# USB_Serial.net
KiCad netlist of a schematic drawn in Altium Designer
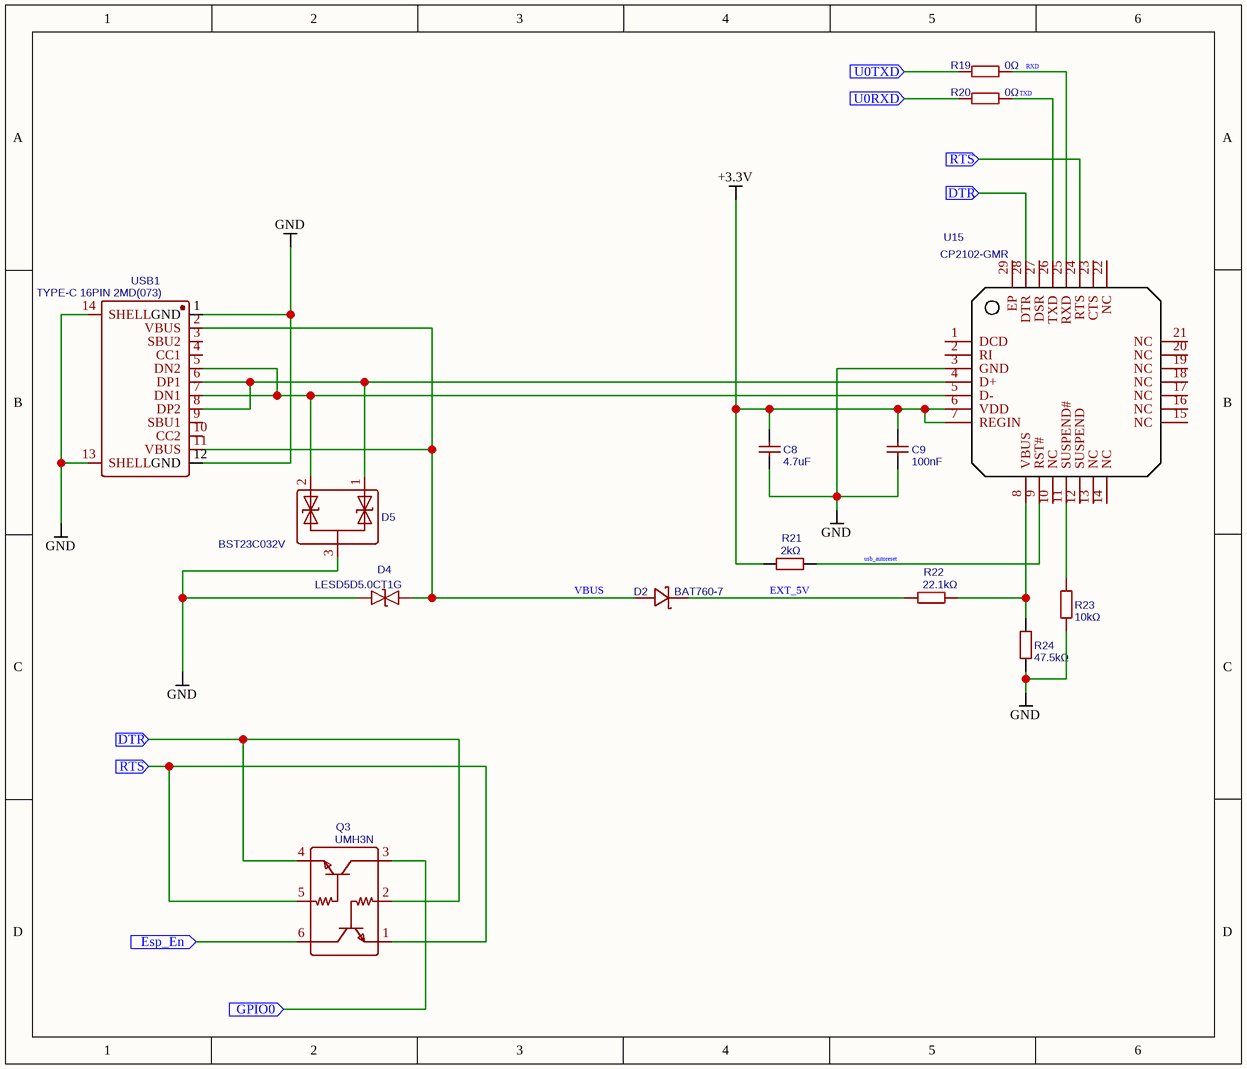
[diagram p0: USB_Serial.schdoc]

(export (version "E")
  (design (tool "Eeschema 10.0.6"))
  (components
    (comp (ref "C8")
      (value "4.7uF")
      (fields (field (name "MANUFACTURER") "FH") (field (name "MANUFACTURER PART") "0603X475K160NT"))
      (libsource (lib "altium-import") (part "root_1_4.7uF_"))
    )
    (comp (ref "C9")
      (value "100nF")
      (fields (field (name "MANUFACTURER") "SAMSUNG") (field (name "MANUFACTURER PART") "CL10B104KO8NNNC"))
      (libsource (lib "altium-import") (part "root_1_100nF_"))
    )
    (comp (ref "D2")
      (value "BAT760-7")
      (fields (field (name "MANUFACTURER") "DIODES") (field (name "CONTRIBUTOR") "LCSC"))
      (libsource (lib "altium-import") (part "root_2_BAT760-7_"))
    )
    (comp (ref "D4")
      (value "LESD5D5.0CT1G")
      (fields (field (name "MANUFACTURER") "Leshan Radio") (field (name "CONTRIBUTOR") "LCSC"))
      (libsource (lib "altium-import") (part "root_0_LESD5D5.0CT1G_"))
    )
    (comp (ref "D5")
      (value "BST23C032V")
      (fields (field (name "MANUFACTURER") "Bourne Semicon (Shenzhen)") (field (name "CONTRIBUTOR") "LCSC"))
      (libsource (lib "altium-import") (part "root_2_BST23C032V_"))
    )
    (comp (ref "Q3")
      (value "UMH3N")
      (fields (field (name "MANUFACTURER") "CJ"))
      (libsource (lib "altium-import") (part "root_1_UMH3N_"))
    )
    (comp (ref "R19")
      (value "0Ω")
      (fields
        (field (name "MANUFACTURER") "FH")
        (field (name "MANUFACTURER PART") "RS-03000FT")
        (field (name "CONTRIBUTOR") "LCSC")
      )
      (libsource (lib "altium-import") (part "root_0_0Ω_"))
    )
    (comp (ref "R20")
      (value "0Ω")
      (fields
        (field (name "MANUFACTURER") "FH")
        (field (name "MANUFACTURER PART") "RS-03000FT")
        (field (name "CONTRIBUTOR") "LCSC")
      )
      (libsource (lib "altium-import") (part "root_0_0Ω_"))
    )
    (comp (ref "R21")
      (value "2kΩ")
      (fields (field (name "MANUFACTURER") "FH") (field (name "MANUFACTURER PART") "RS-03K2001FT"))
      (libsource (lib "altium-import") (part "root_0_2kΩ_"))
    )
    (comp (ref "R22")
      (value "22.1kΩ")
      (fields
        (field (name "MANUFACTURER") "Guangdong Fenghua Advanced Tech")
        (field (name "MANUFACTURER PART") "RS-03K2212FT")
        (field (name "CONTRIBUTOR") "LCSC")
      )
      (libsource (lib "altium-import") (part "root_0_22.1kΩ_"))
    )
    (comp (ref "R23")
      (value "10kΩ")
      (fields
        (field (name "MANUFACTURER") "Guangdong Fenghua Advanced Tech")
        (field (name "MANUFACTURER PART") "RS-03K1002FT")
        (field (name "CONTRIBUTOR") "LCSC")
      )
      (libsource (lib "altium-import") (part "root_1_10kΩ_"))
    )
    (comp (ref "R24")
      (value "47.5kΩ")
      (fields (field (name "MANUFACTURER") "UniOhm") (field (name "MANUFACTURER PART") "0603WAF4752T5E"))
      (libsource (lib "altium-import") (part "root_1_47.5kΩ_"))
    )
    (comp (ref "U15")
      (value "CP2102-GMR")
      (fields (field (name "MANUFACTURER") "SILICON LABS"))
      (libsource (lib "altium-import") (part "root_0_CP2102-GMR_"))
    )
    (comp (ref "USB1")
      (value "TYPE-C 16PIN 2MD(073)")
      (fields (field (name "MANUFACTURER") "SHOU HAN(首韩)") (field (name "CONTRIBUTOR") "LCSC"))
      (libsource (lib "altium-import") (part "root_0_TYPE-C 16PIN 2MD(073)_"))
    )
  )
  (nets
    (net (code "1") (name "+3.3V") (class "Default")
      (node (ref "C8") (pin "2") (pinfunction "2_2") (pintype "passive"))
      (node (ref "C9") (pin "2") (pinfunction "2_2") (pintype "passive"))
      (node (ref "R21") (pin "1") (pinfunction "1_1") (pintype "passive"))
      (node (ref "U15") (pin "6") (pinfunction "VDD_6") (pintype "passive"))
      (node (ref "U15") (pin "7") (pinfunction "REGIN_7") (pintype "passive"))
    )
    (net (code "2") (name "/DTR") (class "Default")
      (node (ref "Q3") (pin "2") (pinfunction "B_2") (pintype "passive"))
      (node (ref "Q3") (pin "4") (pinfunction "E_4") (pintype "passive"))
      (node (ref "U15") (pin "28") (pinfunction "DTR_28") (pintype "passive"))
    )
    (net (code "3") (name "/EXT_5V") (class "Default")
      (node (ref "D2") (pin "1") (pinfunction "1_1") (pintype "passive"))
      (node (ref "R22") (pin "1") (pinfunction "1_1") (pintype "passive"))
    )
    (net (code "4") (name "/Esp_En") (class "Default")
      (node (ref "Q3") (pin "6") (pinfunction "C_6") (pintype "passive"))
    )
    (net (code "5") (name "/GPIO0") (class "Default")
      (node (ref "Q3") (pin "3") (pinfunction "C_3") (pintype "passive"))
    )
    (net (code "6") (name "/RTS") (class "Default")
      (node (ref "Q3") (pin "1") (pinfunction "E_1") (pintype "passive"))
      (node (ref "Q3") (pin "5") (pinfunction "B_5") (pintype "passive"))
      (node (ref "U15") (pin "24") (pinfunction "RTS_24") (pintype "passive"))
    )
    (net (code "7") (name "/RXD") (class "Default")
      (node (ref "R19") (pin "2") (pinfunction "2_2") (pintype "passive"))
      (node (ref "U15") (pin "25") (pinfunction "RXD_25") (pintype "passive"))
    )
    (net (code "8") (name "/TXD") (class "Default")
      (node (ref "R20") (pin "2") (pinfunction "2_2") (pintype "passive"))
      (node (ref "U15") (pin "26") (pinfunction "TXD_26") (pintype "passive"))
    )
    (net (code "9") (name "/U0RXD") (class "Default")
      (node (ref "R20") (pin "1") (pinfunction "1_1") (pintype "passive"))
    )
    (net (code "10") (name "/U0TXD") (class "Default")
      (node (ref "R19") (pin "1") (pinfunction "1_1") (pintype "passive"))
    )
    (net (code "11") (name "/VBUS") (class "Default")
      (node (ref "D2") (pin "2") (pinfunction "2_2") (pintype "passive"))
      (node (ref "D4") (pin "2") (pinfunction "2_2") (pintype "passive"))
      (node (ref "USB1") (pin "11") (pinfunction "VBUS_11") (pintype "passive"))
      (node (ref "USB1") (pin "2") (pinfunction "VBUS_2") (pintype "passive"))
    )
    (net (code "12") (name "/usb_autoreset") (class "Default")
      (node (ref "R21") (pin "2") (pinfunction "2_2") (pintype "passive"))
      (node (ref "U15") (pin "9") (pinfunction "RST#_9") (pintype "passive"))
    )
    (net (code "13") (name "GND") (class "Default")
      (node (ref "C8") (pin "1") (pinfunction "1_1") (pintype "passive"))
      (node (ref "C9") (pin "1") (pinfunction "1_1") (pintype "passive"))
      (node (ref "D4") (pin "1") (pinfunction "1_1") (pintype "passive"))
      (node (ref "D5") (pin "3") (pinfunction "3_3") (pintype "passive"))
      (node (ref "R23") (pin "1") (pinfunction "1_1") (pintype "passive"))
      (node (ref "R24") (pin "1") (pinfunction "1_1") (pintype "passive"))
      (node (ref "U15") (pin "3") (pinfunction "GND_3") (pintype "passive"))
      (node (ref "USB1") (pin "1") (pinfunction "GND_1") (pintype "passive"))
      (node (ref "USB1") (pin "12") (pinfunction "GND_12") (pintype "passive"))
      (node (ref "USB1") (pin "13") (pinfunction "SHELL_13") (pintype "passive"))
      (node (ref "USB1") (pin "14") (pinfunction "SHELL_14") (pintype "passive"))
    )
    (net (code "14") (name "Net-(U15-D+)") (class "Default")
      (node (ref "D5") (pin "1") (pinfunction "1_1") (pintype "passive"))
      (node (ref "U15") (pin "4") (pinfunction "D+_4") (pintype "passive"))
      (node (ref "USB1") (pin "6") (pinfunction "DP1_6") (pintype "passive"))
      (node (ref "USB1") (pin "8") (pinfunction "DP2_8") (pintype "passive"))
    )
    (net (code "15") (name "Net-(U15-D-)") (class "Default")
      (node (ref "D5") (pin "2") (pinfunction "2_2") (pintype "passive"))
      (node (ref "U15") (pin "5") (pinfunction "D-_5") (pintype "passive"))
      (node (ref "USB1") (pin "5") (pinfunction "DN2_5") (pintype "passive"))
      (node (ref "USB1") (pin "7") (pinfunction "DN1_7") (pintype "passive"))
    )
    (net (code "16") (name "Net-(U15-SUSPEND#)") (class "Default")
      (node (ref "R23") (pin "2") (pinfunction "2_2") (pintype "passive"))
      (node (ref "U15") (pin "11") (pinfunction "SUSPEND#_11") (pintype "passive"))
    )
    (net (code "17") (name "Net-(U15-VBUS)") (class "Default")
      (node (ref "R22") (pin "2") (pinfunction "2_2") (pintype "passive"))
      (node (ref "R24") (pin "2") (pinfunction "2_2") (pintype "passive"))
      (node (ref "U15") (pin "8") (pinfunction "VBUS_8") (pintype "passive"))
    )
    (net (code "18") (name "unconnected-(U15-CTS-Pad23)") (class "Default")
      (node (ref "U15") (pin "23") (pinfunction "CTS_23") (pintype "passive"))
    )
    (net (code "19") (name "unconnected-(U15-DCD-Pad1)") (class "Default")
      (node (ref "U15") (pin "1") (pinfunction "DCD_1") (pintype "passive"))
    )
    (net (code "20") (name "unconnected-(U15-DSR-Pad27)") (class "Default")
      (node (ref "U15") (pin "27") (pinfunction "DSR_27") (pintype "passive"))
    )
    (net (code "21") (name "unconnected-(U15-EP-Pad29)") (class "Default")
      (node (ref "U15") (pin "29") (pinfunction "EP_29") (pintype "passive"))
    )
    (net (code "22") (name "unconnected-(U15-NC-Pad10)") (class "Default")
      (node (ref "U15") (pin "10") (pinfunction "NC_10") (pintype "passive"))
    )
    (net (code "23") (name "unconnected-(U15-NC-Pad13)") (class "Default")
      (node (ref "U15") (pin "13") (pinfunction "NC_13") (pintype "passive"))
    )
    (net (code "24") (name "unconnected-(U15-NC-Pad14)") (class "Default")
      (node (ref "U15") (pin "14") (pinfunction "NC_14") (pintype "passive"))
    )
    (net (code "25") (name "unconnected-(U15-NC-Pad15)") (class "Default")
      (node (ref "U15") (pin "15") (pinfunction "NC_15") (pintype "passive"))
    )
    (net (code "26") (name "unconnected-(U15-NC-Pad16)") (class "Default")
      (node (ref "U15") (pin "16") (pinfunction "NC_16") (pintype "passive"))
    )
    (net (code "27") (name "unconnected-(U15-NC-Pad17)") (class "Default")
      (node (ref "U15") (pin "17") (pinfunction "NC_17") (pintype "passive"))
    )
    (net (code "28") (name "unconnected-(U15-NC-Pad18)") (class "Default")
      (node (ref "U15") (pin "18") (pinfunction "NC_18") (pintype "passive"))
    )
    (net (code "29") (name "unconnected-(U15-NC-Pad19)") (class "Default")
      (node (ref "U15") (pin "19") (pinfunction "NC_19") (pintype "passive"))
    )
    (net (code "30") (name "unconnected-(U15-NC-Pad20)") (class "Default")
      (node (ref "U15") (pin "20") (pinfunction "NC_20") (pintype "passive"))
    )
    (net (code "31") (name "unconnected-(U15-NC-Pad21)") (class "Default")
      (node (ref "U15") (pin "21") (pinfunction "NC_21") (pintype "passive"))
    )
    (net (code "32") (name "unconnected-(U15-NC-Pad22)") (class "Default")
      (node (ref "U15") (pin "22") (pinfunction "NC_22") (pintype "passive"))
    )
    (net (code "33") (name "unconnected-(U15-RI-Pad2)") (class "Default")
      (node (ref "U15") (pin "2") (pinfunction "RI_2") (pintype "passive"))
    )
    (net (code "34") (name "unconnected-(U15-SUSPEND-Pad12)") (class "Default")
      (node (ref "U15") (pin "12") (pinfunction "SUSPEND_12") (pintype "passive"))
    )
    (net (code "35") (name "unconnected-(USB1-CC1-Pad4)") (class "Default")
      (node (ref "USB1") (pin "4") (pinfunction "CC1_4") (pintype "passive"))
    )
    (net (code "36") (name "unconnected-(USB1-CC2-Pad10)") (class "Default")
      (node (ref "USB1") (pin "10") (pinfunction "CC2_10") (pintype "passive"))
    )
    (net (code "37") (name "unconnected-(USB1-SBU1-Pad9)") (class "Default")
      (node (ref "USB1") (pin "9") (pinfunction "SBU1_9") (pintype "passive"))
    )
    (net (code "38") (name "unconnected-(USB1-SBU2-Pad3)") (class "Default")
      (node (ref "USB1") (pin "3") (pinfunction "SBU2_3") (pintype "passive"))
    )
  )
)
